# triac.net
KiCad netlist of a schematic drawn in EAGLE
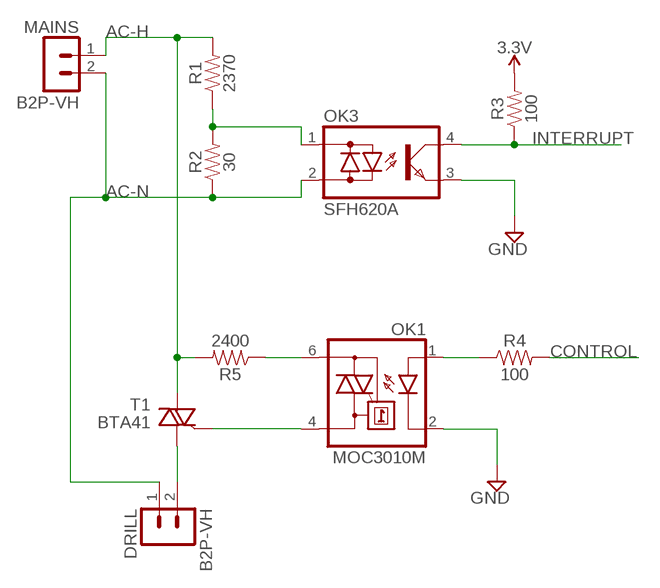
[diagram p0: schematic, sheet 1]

(export (version "E")
  (design (tool "Eeschema 10.0.6"))
  (components
    (comp (ref "DRILL")
      (value "B2P-VH")
      (footprint "eagle-import:B2P-VH")
      (libsource (lib "eagle-import") (part "B2P-VH"))
    )
    (comp (ref "MAINS")
      (value "B2P-VH")
      (footprint "eagle-import:B2P-VH")
      (libsource (lib "eagle-import") (part "B2P-VH"))
    )
    (comp (ref "OK1")
      (value "MOC3010M")
      (footprint "eagle-import:DIL06")
      (fields (field (name "MF") "FAIRCHILD SEMICONDUCTOR") (field (name "MPN") "MOC3010-M"))
      (libsource (lib "eagle-import") (part "MOC30M10"))
    )
    (comp (ref "OK3")
      (value "SFH620A")
      (footprint "eagle-import:DIL04")
      (fields (field (name "MPN") "SFH620A-2"))
      (libsource (lib "eagle-import") (part "SFH620A"))
    )
    (comp (ref "R1")
      (value "2370")
      (footprint "eagle-import:0805")
      (libsource (lib "eagle-import") (part "0.3OHM-0805-1/8W-1%"))
    )
    (comp (ref "R2")
      (value "30")
      (footprint "eagle-import:0805")
      (libsource (lib "eagle-import") (part "0.3OHM-0805-1/8W-1%"))
    )
    (comp (ref "R3")
      (value "100")
      (footprint "eagle-import:0805")
      (libsource (lib "eagle-import") (part "0.3OHM-0805-1/8W-1%"))
    )
    (comp (ref "R4")
      (value "100")
      (footprint "eagle-import:0805")
      (libsource (lib "eagle-import") (part "0.3OHM-0805-1/8W-1%"))
    )
    (comp (ref "R5")
      (value "2400")
      (footprint "eagle-import:0805")
      (libsource (lib "eagle-import") (part "0.3OHM-0805-1/8W-1%"))
    )
    (comp (ref "T1")
      (value "BTA41")
      (footprint "eagle-import:TOP3L-1")
      (libsource (lib "eagle-import") (part "BTA26-H"))
    )
  )
  (nets
    (net (code "1") (name "/AC-H") (class "Default")
      (node (ref "MAINS") (pin "1") (pinfunction "1_1") (pintype "passive"))
      (node (ref "R1") (pin "2") (pinfunction "2_2") (pintype "passive"))
      (node (ref "R5") (pin "2") (pinfunction "2_2") (pintype "passive"))
      (node (ref "T1") (pin "A2") (pinfunction "A2_A2") (pintype "passive"))
    )
    (net (code "2") (name "/AC-N") (class "Default")
      (node (ref "DRILL") (pin "1") (pinfunction "1_1") (pintype "passive"))
      (node (ref "MAINS") (pin "2") (pinfunction "2_2") (pintype "passive"))
      (node (ref "OK3") (pin "2") (pinfunction "AC2_2") (pintype "passive"))
      (node (ref "R2") (pin "1") (pinfunction "1_1") (pintype "passive"))
    )
    (net (code "3") (name "/CONTROL") (class "Default")
      (node (ref "R4") (pin "2") (pinfunction "2_2") (pintype "passive"))
    )
    (net (code "4") (name "/INTERRUPT") (class "Default")
      (node (ref "OK3") (pin "4") (pinfunction "C_4") (pintype "passive"))
      (node (ref "R3") (pin "1") (pinfunction "1_1") (pintype "passive"))
    )
    (net (code "5") (name "3.3V") (class "Default")
      (node (ref "R3") (pin "2") (pinfunction "2_2") (pintype "passive"))
    )
    (net (code "6") (name "GND") (class "Default")
      (node (ref "OK1") (pin "2") (pinfunction "C_2") (pintype "passive"))
      (node (ref "OK3") (pin "3") (pinfunction "E_3") (pintype "passive"))
    )
    (net (code "7") (name "Net-(DRILL-Pad2)") (class "Default")
      (node (ref "DRILL") (pin "2") (pinfunction "2_2") (pintype "passive"))
      (node (ref "T1") (pin "A1") (pinfunction "A1_A1") (pintype "passive"))
    )
    (net (code "8") (name "Net-(OK1-A)") (class "Default")
      (node (ref "OK1") (pin "1") (pinfunction "A_1") (pintype "passive"))
      (node (ref "R4") (pin "1") (pinfunction "1_1") (pintype "passive"))
    )
    (net (code "9") (name "Net-(OK1-A1)") (class "Default")
      (node (ref "OK1") (pin "4") (pinfunction "A1_4") (pintype "passive"))
      (node (ref "T1") (pin "G") (pinfunction "G_G") (pintype "passive"))
    )
    (net (code "10") (name "Net-(OK1-A2)") (class "Default")
      (node (ref "OK1") (pin "6") (pinfunction "A2_6") (pintype "passive"))
      (node (ref "R5") (pin "1") (pinfunction "1_1") (pintype "passive"))
    )
    (net (code "11") (name "Net-(OK3-AC1)") (class "Default")
      (node (ref "OK3") (pin "1") (pinfunction "AC1_1") (pintype "passive"))
      (node (ref "R1") (pin "1") (pinfunction "1_1") (pintype "passive"))
      (node (ref "R2") (pin "2") (pinfunction "2_2") (pintype "passive"))
    )
  )
)
